# 12-POWER-P12V.net
KiCad netlist of a schematic drawn in Altium Designer
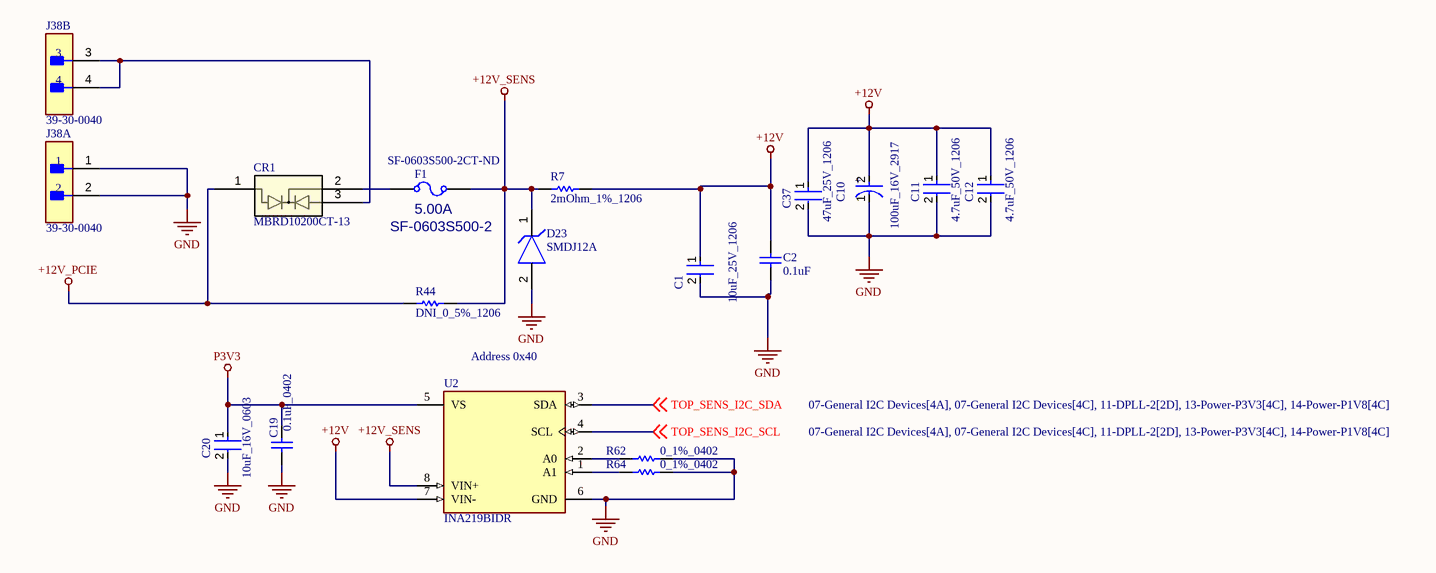
[diagram p0: 12-POWER-P12V.SchDoc]

(export (version "E")
  (design (tool "Eeschema 10.0.6"))
  (components
    (comp (ref "C1")
      (value "10uF_25V_1206")
      (footprint "FP-MK316L-MFG")
      (description "CAP CER 10UF 25V X7R 1206")
      (fields (field (name "TOLERANCE") "10%"))
      (libsource (lib "Altium Content Vault") (part "11868f565c42a9108669ba33697ecf6"))
    )
    (comp (ref "C2")
      (value "0.1uF")
      (footprint "CAPC1608X87X45ML20T05")
      (description "C0603X104K5RACAUTO")
      (fields (field (name "MANUFACTURER") "Kemet"))
      (libsource (lib "Altium Content Vault") (part "CAP"))
    )
    (comp (ref "C10")
      (value "100uF_16V_2917")
      (footprint "FP-T495D107K016ATE125-MFG")
      (description "CAP TANT 100UF 10% 16V 2917")
      (fields (field (name "VOLTAGE") "16V") (field (name "TOLERANCE") "10%"))
      (libsource (lib "Altium Content Vault") (part "a00bbbee19879c290e62620ae7e47b1"))
    )
    (comp (ref "C11")
      (value "4.7uF_50V_1206")
      (footprint "FP-GRM31C-0_2-e0_3_0_8-IPC_C")
      (description "Chip Multilayer Ceramic Capacitors for General Purpose, 1206, 4.7uF, X7R, 15%, 10%, 50V")
      (fields (field (name "VOLTAGE") "50V") (field (name "TOLERANCE") "10%"))
      (libsource (lib "Altium Content Vault") (part "02cd4be3c70576c341d710602a673aa"))
    )
    (comp (ref "C12")
      (value "4.7uF_50V_1206")
      (footprint "FP-GRM31C-0_2-e0_3_0_8-IPC_C")
      (description "Chip Multilayer Ceramic Capacitors for General Purpose, 1206, 4.7uF, X7R, 15%, 10%, 50V")
      (fields (field (name "VOLTAGE") "50V") (field (name "TOLERANCE") "10%"))
      (libsource (lib "Altium Content Vault") (part "02cd4be3c70576c341d710602a673aa"))
    )
    (comp (ref "C19")
      (value "0.1uF_0402")
      (footprint "CAPC1005X56X25NL10T15")
      (fields
        (field (name "PART NUMBER") "LD02YD104KAB2A")
        (field (name "MANUFACTURER") "AVX Interconnect / Elco")
      )
      (libsource (lib "Altium Content Vault") (part "CAP"))
    )
    (comp (ref "C20")
      (value "10uF_16V_0603")
      (footprint "FP-0603-L_1_6_0_2-W_0_8_0-MFG")
      (description "Multilayer Ceramic Capacitor 10uF 16V X5R 20% SMD 0603 T/R")
      (fields (field (name "TOLERANCE") "20%"))
      (libsource (lib "Altium Content Vault") (part "b4654b650e69147ec39a6b967a45e02"))
    )
    (comp (ref "C37")
      (value "47uF_25V_1206")
      (footprint "FP-C3216-160-0_2-MFG")
      (description "Multilayer Ceramic Capacitors 47uF ±20% 25V X5R SMD 1206")
      (fields (field (name "VOLTAGE") "25V") (field (name "TOLERANCE") "20%"))
      (libsource (lib "Altium Content Vault") (part "11868f565c42a9108669ba33697ecf6"))
    )
    (comp (ref "CR1")
      (value "MBRD10200CT-13")
      (footprint "TO252(DPAK)_DIO")
      (description "No Description Available")
      (libsource (lib "MBRD10200CT-13") (part "MBRD10200CT-13"))
    )
    (comp (ref "D23")
      (value "SMDJ12A")
      (footprint "FP-DO-214AB_SMC_J-Bend-MFG")
      (description "TVS DIODE 12V 19.9V DO214AB")
      (libsource (lib "Altium Content Vault") (part "673ecd2ea4d7fb87b4005b0cb348b7d"))
    )
    (comp (ref "F1")
      (value "5.00A")
      (footprint "FUSM1608X60N")
      (description "FUSE SLOW 5.00A 32V M 0603")
      (fields
        (field (name "MFG PART NUM") "SF-0603S500-2")
        (field (name "VALENTIUM PART NUM") "<VALENTIUM>")
        (field (name "SUPPLIER PART NUMBER 1") "SF-0603S500-2CT-ND")
        (field (name "Comment") "FUSE_0603_5.00A")
      )
      (libsource (lib "Passives") (part "FUSE_0603_2.00A"))
    )
    (comp (ref "J38")
      (value "39-30-0040")
      (footprint "FP-39-30-0040-MFG")
      (description "CONN HEADER R/A 4POS 4.2MM")
      (fields
        (field (name "OCTOPART") "https://octopart.com/39-30-0040-molex-277428")
        (field (name "MANUFACTURER") "Molex")
      )
      (libsource (lib "Altium Content Vault") (part "ac72c5313ea981db199dbd0e8237b04"))
    )
    (comp (ref "R7")
      (value "2mOhm_1%_1206")
      (footprint "RESC3216X89X64NL25T25")
      (fields (field (name "MANUFACTURER") "Vishay Dale") (field (name "PART NUMBER") "WSL12062L000FEA18"))
      (libsource (lib "Altium Content Vault") (part "RES"))
    )
    (comp (ref "R44")
      (value "DNI_0_5%_1206")
      (footprint "RESC3116X65X50ML20T20")
      (fields (field (name "PART NUMBER") "CRCW12060000Z0EAHP") (field (name "MANUFACTURER") "Vishay Dale"))
      (libsource (lib "Altium Content Vault") (part "RES"))
    )
    (comp (ref "R62")
      (value "0_1%_0402")
      (footprint "RESC1005X40X25LL05T05")
      (description "Chip Resistor, 0 Ohm, 0.1 W, -55 to 155 degC, 0402 (1005 Metric), RoHS, Tape and Reel")
      (fields (field (name "MANUFACTURER") "Panasonic") (field (name "TOLERANCE") "5%"))
      (libsource (lib "Altium Content Vault") (part "RES-2"))
    )
    (comp (ref "R64")
      (value "0_1%_0402")
      (footprint "RESC1005X40X25LL05T05")
      (description "Chip Resistor, 0 Ohm, 0.1 W, -55 to 155 degC, 0402 (1005 Metric), RoHS, Tape and Reel")
      (fields (field (name "MANUFACTURER") "Panasonic") (field (name "TOLERANCE") "5%"))
      (libsource (lib "Altium Content Vault") (part "RES-2"))
    )
    (comp (ref "U2")
      (value "INA219BIDR")
      (footprint "FP-D0008A-MFG")
      (description "IC MONITOR PWR/CURR BIDIR 8-SOIC")
      (libsource (lib "Altium Content Vault") (part "41cc1aee4cbc9fa2660a15773fa0e79"))
    )
  )
  (nets
    (net (code "1") (name "+12V") (class "Default")
      (node (ref "C1") (pin "1") (pinfunction "1_1") (pintype "passive"))
      (node (ref "C10") (pin "2") (pinfunction "A_2") (pintype "passive"))
      (node (ref "C11") (pin "1") (pinfunction "1_1") (pintype "passive"))
      (node (ref "C12") (pin "1") (pinfunction "1_1") (pintype "passive"))
      (node (ref "C2") (pin "2") (pinfunction "2_2") (pintype "passive"))
      (node (ref "C37") (pin "1") (pinfunction "1_1") (pintype "passive"))
      (node (ref "R7") (pin "2") (pinfunction "2_2") (pintype "passive"))
      (node (ref "U2") (pin "7") (pinfunction "VIN-_7") (pintype "input"))
    )
    (net (code "2") (name "+12V_PCIE") (class "Default")
      (node (ref "CR1") (pin "1") (pinfunction "1_1") (pintype "passive"))
      (node (ref "R44") (pin "1") (pinfunction "1_1") (pintype "passive"))
    )
    (net (code "3") (name "+12V_SENS") (class "Default")
      (node (ref "D23") (pin "1") (pinfunction "C_1") (pintype "passive"))
      (node (ref "F1") (pin "2") (pinfunction "2_2") (pintype "passive"))
      (node (ref "R44") (pin "2") (pinfunction "2_2") (pintype "passive"))
      (node (ref "R7") (pin "1") (pinfunction "1_1") (pintype "passive"))
      (node (ref "U2") (pin "8") (pinfunction "VIN+_8") (pintype "input"))
    )
    (net (code "4") (name "GND") (class "Default")
      (node (ref "C1") (pin "2") (pinfunction "2_2") (pintype "passive"))
      (node (ref "C10") (pin "1") (pinfunction "C_1") (pintype "passive"))
      (node (ref "C11") (pin "2") (pinfunction "2_2") (pintype "passive"))
      (node (ref "C12") (pin "2") (pinfunction "2_2") (pintype "passive"))
      (node (ref "C19") (pin "1") (pinfunction "1_1") (pintype "passive"))
      (node (ref "C2") (pin "1") (pinfunction "1_1") (pintype "passive"))
      (node (ref "C20") (pin "2") (pinfunction "2_2") (pintype "passive"))
      (node (ref "C37") (pin "2") (pinfunction "2_2") (pintype "passive"))
      (node (ref "D23") (pin "2") (pinfunction "A_2") (pintype "passive"))
      (node (ref "J38") (pin "1") (pinfunction "1_1") (pintype "passive"))
      (node (ref "J38") (pin "2") (pinfunction "2_2") (pintype "passive"))
      (node (ref "R62") (pin "2") (pinfunction "2_2") (pintype "passive"))
      (node (ref "R64") (pin "2") (pinfunction "2_2") (pintype "passive"))
      (node (ref "U2") (pin "6") (pinfunction "GND_6") (pintype "power_in"))
    )
    (net (code "5") (name "Net-(CR1-Pad2)") (class "Default")
      (node (ref "CR1") (pin "2") (pinfunction "2_2") (pintype "passive"))
      (node (ref "F1") (pin "1") (pinfunction "1_1") (pintype "passive"))
    )
    (net (code "6") (name "Net-(CR1-Pad3)") (class "Default")
      (node (ref "CR1") (pin "3") (pinfunction "3_3") (pintype "passive"))
      (node (ref "J38") (pin "3") (pinfunction "3_3") (pintype "passive"))
      (node (ref "J38") (pin "4") (pinfunction "4_4") (pintype "passive"))
    )
    (net (code "7") (name "Net-(U2-A0)") (class "Default")
      (node (ref "R62") (pin "1") (pinfunction "1_1") (pintype "passive"))
      (node (ref "U2") (pin "2") (pinfunction "A0_2") (pintype "input"))
    )
    (net (code "8") (name "Net-(U2-A1)") (class "Default")
      (node (ref "R64") (pin "1") (pinfunction "1_1") (pintype "passive"))
      (node (ref "U2") (pin "1") (pinfunction "A1_1") (pintype "input"))
    )
    (net (code "9") (name "P3V3") (class "Default")
      (node (ref "C19") (pin "2") (pinfunction "2_2") (pintype "passive"))
      (node (ref "C20") (pin "1") (pinfunction "1_1") (pintype "passive"))
      (node (ref "U2") (pin "5") (pinfunction "VS_5") (pintype "power_in"))
    )
    (net (code "10") (name "TOP_SENS_I2C_SCL") (class "Default")
      (node (ref "U2") (pin "4") (pinfunction "SCL_4") (pintype "bidirectional"))
    )
    (net (code "11") (name "TOP_SENS_I2C_SDA") (class "Default")
      (node (ref "U2") (pin "3") (pinfunction "SDA_3") (pintype "bidirectional"))
    )
  )
)
